# LPCB235_-_BRAKE_LIMIT_SW.net
KiCad netlist of a schematic drawn in Altium Designer
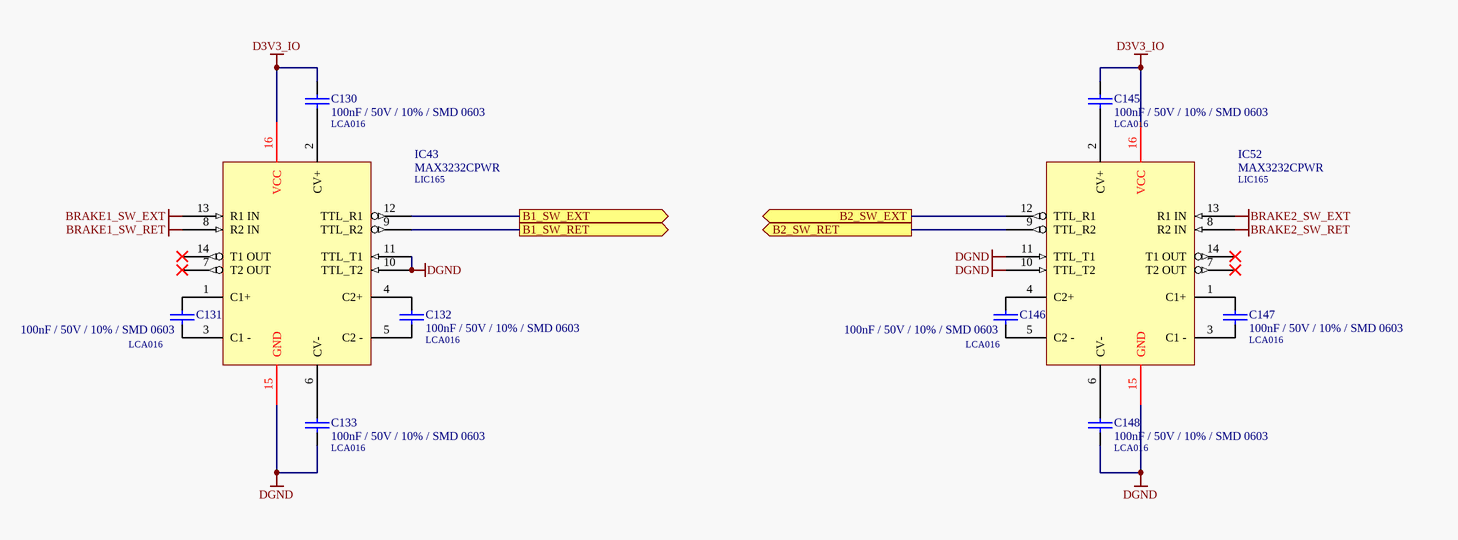
[diagram p0: LPCB235 - BRAKE LIMIT SW.SchDoc]

(export (version "E")
  (design (tool "Eeschema 10.0.6"))
  (components
    (comp (ref "C130")
      (value "100nF / 50V / 10% / SMD 0603")
      (footprint "LFP011__CC1608-0603-IPC7351_B")
      (description "Capacitor, Ceramic Chip, 100nF (0.1uF), 50V, 5%, SMD 0603 [LCA016]")
      (fields (field (name "LDL_NUMBER") "LCA016"))
      (libsource (lib "LDL_Capacitors") (part "100nF / 50V / 10% / SMD 0603"))
    )
    (comp (ref "C131")
      (value "100nF / 50V / 10% / SMD 0603")
      (footprint "LFP011__CC1608-0603-IPC7351_B")
      (description "Capacitor, Ceramic Chip, 100nF (0.1uF), 50V, 5%, SMD 0603 [LCA016]")
      (fields (field (name "LDL_NUMBER") "LCA016"))
      (libsource (lib "LDL_Capacitors") (part "100nF / 50V / 10% / SMD 0603"))
    )
    (comp (ref "C132")
      (value "100nF / 50V / 10% / SMD 0603")
      (footprint "LFP011__CC1608-0603-IPC7351_B")
      (description "Capacitor, Ceramic Chip, 100nF (0.1uF), 50V, 5%, SMD 0603 [LCA016]")
      (fields (field (name "LDL_NUMBER") "LCA016"))
      (libsource (lib "LDL_Capacitors") (part "100nF / 50V / 10% / SMD 0603"))
    )
    (comp (ref "C133")
      (value "100nF / 50V / 10% / SMD 0603")
      (footprint "LFP011__CC1608-0603-IPC7351_B")
      (description "Capacitor, Ceramic Chip, 100nF (0.1uF), 50V, 5%, SMD 0603 [LCA016]")
      (fields (field (name "LDL_NUMBER") "LCA016"))
      (libsource (lib "LDL_Capacitors") (part "100nF / 50V / 10% / SMD 0603"))
    )
    (comp (ref "C145")
      (value "100nF / 50V / 10% / SMD 0603")
      (footprint "LFP011__CC1608-0603-IPC7351_B")
      (description "Capacitor, Ceramic Chip, 100nF (0.1uF), 50V, 5%, SMD 0603 [LCA016]")
      (fields (field (name "LDL_NUMBER") "LCA016"))
      (libsource (lib "LDL_Capacitors") (part "100nF / 50V / 10% / SMD 0603"))
    )
    (comp (ref "C146")
      (value "100nF / 50V / 10% / SMD 0603")
      (footprint "LFP011__CC1608-0603-IPC7351_B")
      (description "Capacitor, Ceramic Chip, 100nF (0.1uF), 50V, 5%, SMD 0603 [LCA016]")
      (fields (field (name "LDL_NUMBER") "LCA016"))
      (libsource (lib "LDL_Capacitors") (part "100nF / 50V / 10% / SMD 0603"))
    )
    (comp (ref "C147")
      (value "100nF / 50V / 10% / SMD 0603")
      (footprint "LFP011__CC1608-0603-IPC7351_B")
      (description "Capacitor, Ceramic Chip, 100nF (0.1uF), 50V, 5%, SMD 0603 [LCA016]")
      (fields (field (name "LDL_NUMBER") "LCA016"))
      (libsource (lib "LDL_Capacitors") (part "100nF / 50V / 10% / SMD 0603"))
    )
    (comp (ref "C148")
      (value "100nF / 50V / 10% / SMD 0603")
      (footprint "LFP011__CC1608-0603-IPC7351_B")
      (description "Capacitor, Ceramic Chip, 100nF (0.1uF), 50V, 5%, SMD 0603 [LCA016]")
      (fields (field (name "LDL_NUMBER") "LCA016"))
      (libsource (lib "LDL_Capacitors") (part "100nF / 50V / 10% / SMD 0603"))
    )
    (comp (ref "IC43")
      (value "MAX3232CPWR")
      (footprint "LFP049__TSSOP-16")
      (description "IC, RS232 Line Driver, 3.3V, SMD TSSOP16 [LIC165]")
      (fields (field (name "LDL_NUMBER") "LIC165"))
      (libsource (lib "") (part "MAX3232CPWR_1"))
    )
    (comp (ref "IC52")
      (value "MAX3232CPWR")
      (footprint "LFP049__TSSOP-16")
      (description "IC, RS232 Line Driver, 3.3V, SMD TSSOP16")
      (fields (field (name "LDL_NUMBER") "LIC165"))
      (libsource (lib "LDL_Semiconductors") (part "MAX3232CPWR"))
    )
  )
  (nets
    (net (code "1") (name "/B1_SW_EXT") (class "Default")
      (node (ref "IC43") (pin "12") (pinfunction "TTL_R1_12") (pintype "output"))
    )
    (net (code "2") (name "/B1_SW_RET") (class "Default")
      (node (ref "IC43") (pin "9") (pinfunction "TTL_R2_9") (pintype "output"))
    )
    (net (code "3") (name "/B2_SW_EXT") (class "Default")
      (node (ref "IC52") (pin "12") (pinfunction "TTL_R1_12") (pintype "output"))
    )
    (net (code "4") (name "/B2_SW_RET") (class "Default")
      (node (ref "IC52") (pin "9") (pinfunction "TTL_R2_9") (pintype "output"))
    )
    (net (code "5") (name "BRAKE1_SW_EXT") (class "Default")
      (node (ref "IC43") (pin "13") (pinfunction "R1_IN_13") (pintype "input"))
    )
    (net (code "6") (name "BRAKE1_SW_RET") (class "Default")
      (node (ref "IC43") (pin "8") (pinfunction "R2_IN_8") (pintype "input"))
    )
    (net (code "7") (name "BRAKE2_SW_EXT") (class "Default")
      (node (ref "IC52") (pin "13") (pinfunction "R1_IN_13") (pintype "input"))
    )
    (net (code "8") (name "BRAKE2_SW_RET") (class "Default")
      (node (ref "IC52") (pin "8") (pinfunction "R2_IN_8") (pintype "input"))
    )
    (net (code "9") (name "D3V3_IO") (class "Default")
      (node (ref "C130") (pin "1") (pintype "passive"))
      (node (ref "C145") (pin "1") (pintype "passive"))
      (node (ref "IC43") (pin "16") (pinfunction "VCC_16") (pintype "power_in"))
      (node (ref "IC52") (pin "16") (pinfunction "VCC_16") (pintype "power_in"))
    )
    (net (code "10") (name "DGND") (class "Default")
      (node (ref "C133") (pin "2") (pintype "passive"))
      (node (ref "C148") (pin "2") (pintype "passive"))
      (node (ref "IC43") (pin "10") (pinfunction "TTL_T2_10") (pintype "input"))
      (node (ref "IC43") (pin "11") (pinfunction "TTL_T1_11") (pintype "input"))
      (node (ref "IC43") (pin "15") (pinfunction "GND_15") (pintype "power_in"))
      (node (ref "IC52") (pin "10") (pinfunction "TTL_T2_10") (pintype "input"))
      (node (ref "IC52") (pin "11") (pinfunction "TTL_T1_11") (pintype "input"))
      (node (ref "IC52") (pin "15") (pinfunction "GND_15") (pintype "power_in"))
    )
    (net (code "11") (name "Net-(IC43-C1+)") (class "Default")
      (node (ref "C131") (pin "1") (pintype "passive"))
      (node (ref "IC43") (pin "1") (pinfunction "C1+_1") (pintype "passive"))
    )
    (net (code "12") (name "Net-(IC43-C1_-)") (class "Default")
      (node (ref "C131") (pin "2") (pintype "passive"))
      (node (ref "IC43") (pin "3") (pinfunction "C1_-_3") (pintype "passive"))
    )
    (net (code "13") (name "Net-(IC43-C2+)") (class "Default")
      (node (ref "C132") (pin "1") (pintype "passive"))
      (node (ref "IC43") (pin "4") (pinfunction "C2+_4") (pintype "passive"))
    )
    (net (code "14") (name "Net-(IC43-C2_-)") (class "Default")
      (node (ref "C132") (pin "2") (pintype "passive"))
      (node (ref "IC43") (pin "5") (pinfunction "C2_-_5") (pintype "passive"))
    )
    (net (code "15") (name "Net-(IC43-CV+)") (class "Default")
      (node (ref "C130") (pin "2") (pintype "passive"))
      (node (ref "IC43") (pin "2") (pinfunction "CV+_2") (pintype "passive"))
    )
    (net (code "16") (name "Net-(IC43-CV-)") (class "Default")
      (node (ref "C133") (pin "1") (pintype "passive"))
      (node (ref "IC43") (pin "6") (pinfunction "CV-_6") (pintype "passive"))
    )
    (net (code "17") (name "Net-(IC52-C1+)") (class "Default")
      (node (ref "C147") (pin "1") (pintype "passive"))
      (node (ref "IC52") (pin "1") (pinfunction "C1+_1") (pintype "passive"))
    )
    (net (code "18") (name "Net-(IC52-C1_-)") (class "Default")
      (node (ref "C147") (pin "2") (pintype "passive"))
      (node (ref "IC52") (pin "3") (pinfunction "C1_-_3") (pintype "passive"))
    )
    (net (code "19") (name "Net-(IC52-C2+)") (class "Default")
      (node (ref "C146") (pin "1") (pintype "passive"))
      (node (ref "IC52") (pin "4") (pinfunction "C2+_4") (pintype "passive"))
    )
    (net (code "20") (name "Net-(IC52-C2_-)") (class "Default")
      (node (ref "C146") (pin "2") (pintype "passive"))
      (node (ref "IC52") (pin "5") (pinfunction "C2_-_5") (pintype "passive"))
    )
    (net (code "21") (name "Net-(IC52-CV+)") (class "Default")
      (node (ref "C145") (pin "2") (pintype "passive"))
      (node (ref "IC52") (pin "2") (pinfunction "CV+_2") (pintype "passive"))
    )
    (net (code "22") (name "Net-(IC52-CV-)") (class "Default")
      (node (ref "C148") (pin "1") (pintype "passive"))
      (node (ref "IC52") (pin "6") (pinfunction "CV-_6") (pintype "passive"))
    )
    (net (code "23") (name "unconnected-(IC43-T1_OUT-Pad14)") (class "Default")
      (node (ref "IC43") (pin "14") (pinfunction "T1_OUT_14") (pintype "output+no_connect"))
    )
    (net (code "24") (name "unconnected-(IC43-T2_OUT-Pad7)") (class "Default")
      (node (ref "IC43") (pin "7") (pinfunction "T2_OUT_7") (pintype "output+no_connect"))
    )
    (net (code "25") (name "unconnected-(IC52-T1_OUT-Pad14)") (class "Default")
      (node (ref "IC52") (pin "14") (pinfunction "T1_OUT_14") (pintype "output+no_connect"))
    )
    (net (code "26") (name "unconnected-(IC52-T2_OUT-Pad7)") (class "Default")
      (node (ref "IC52") (pin "7") (pinfunction "T2_OUT_7") (pintype "output+no_connect"))
    )
  )
)
